# 1-Schematic_5_band_eq_adapter.net
KiCad netlist of a schematic drawn in EasyEDA
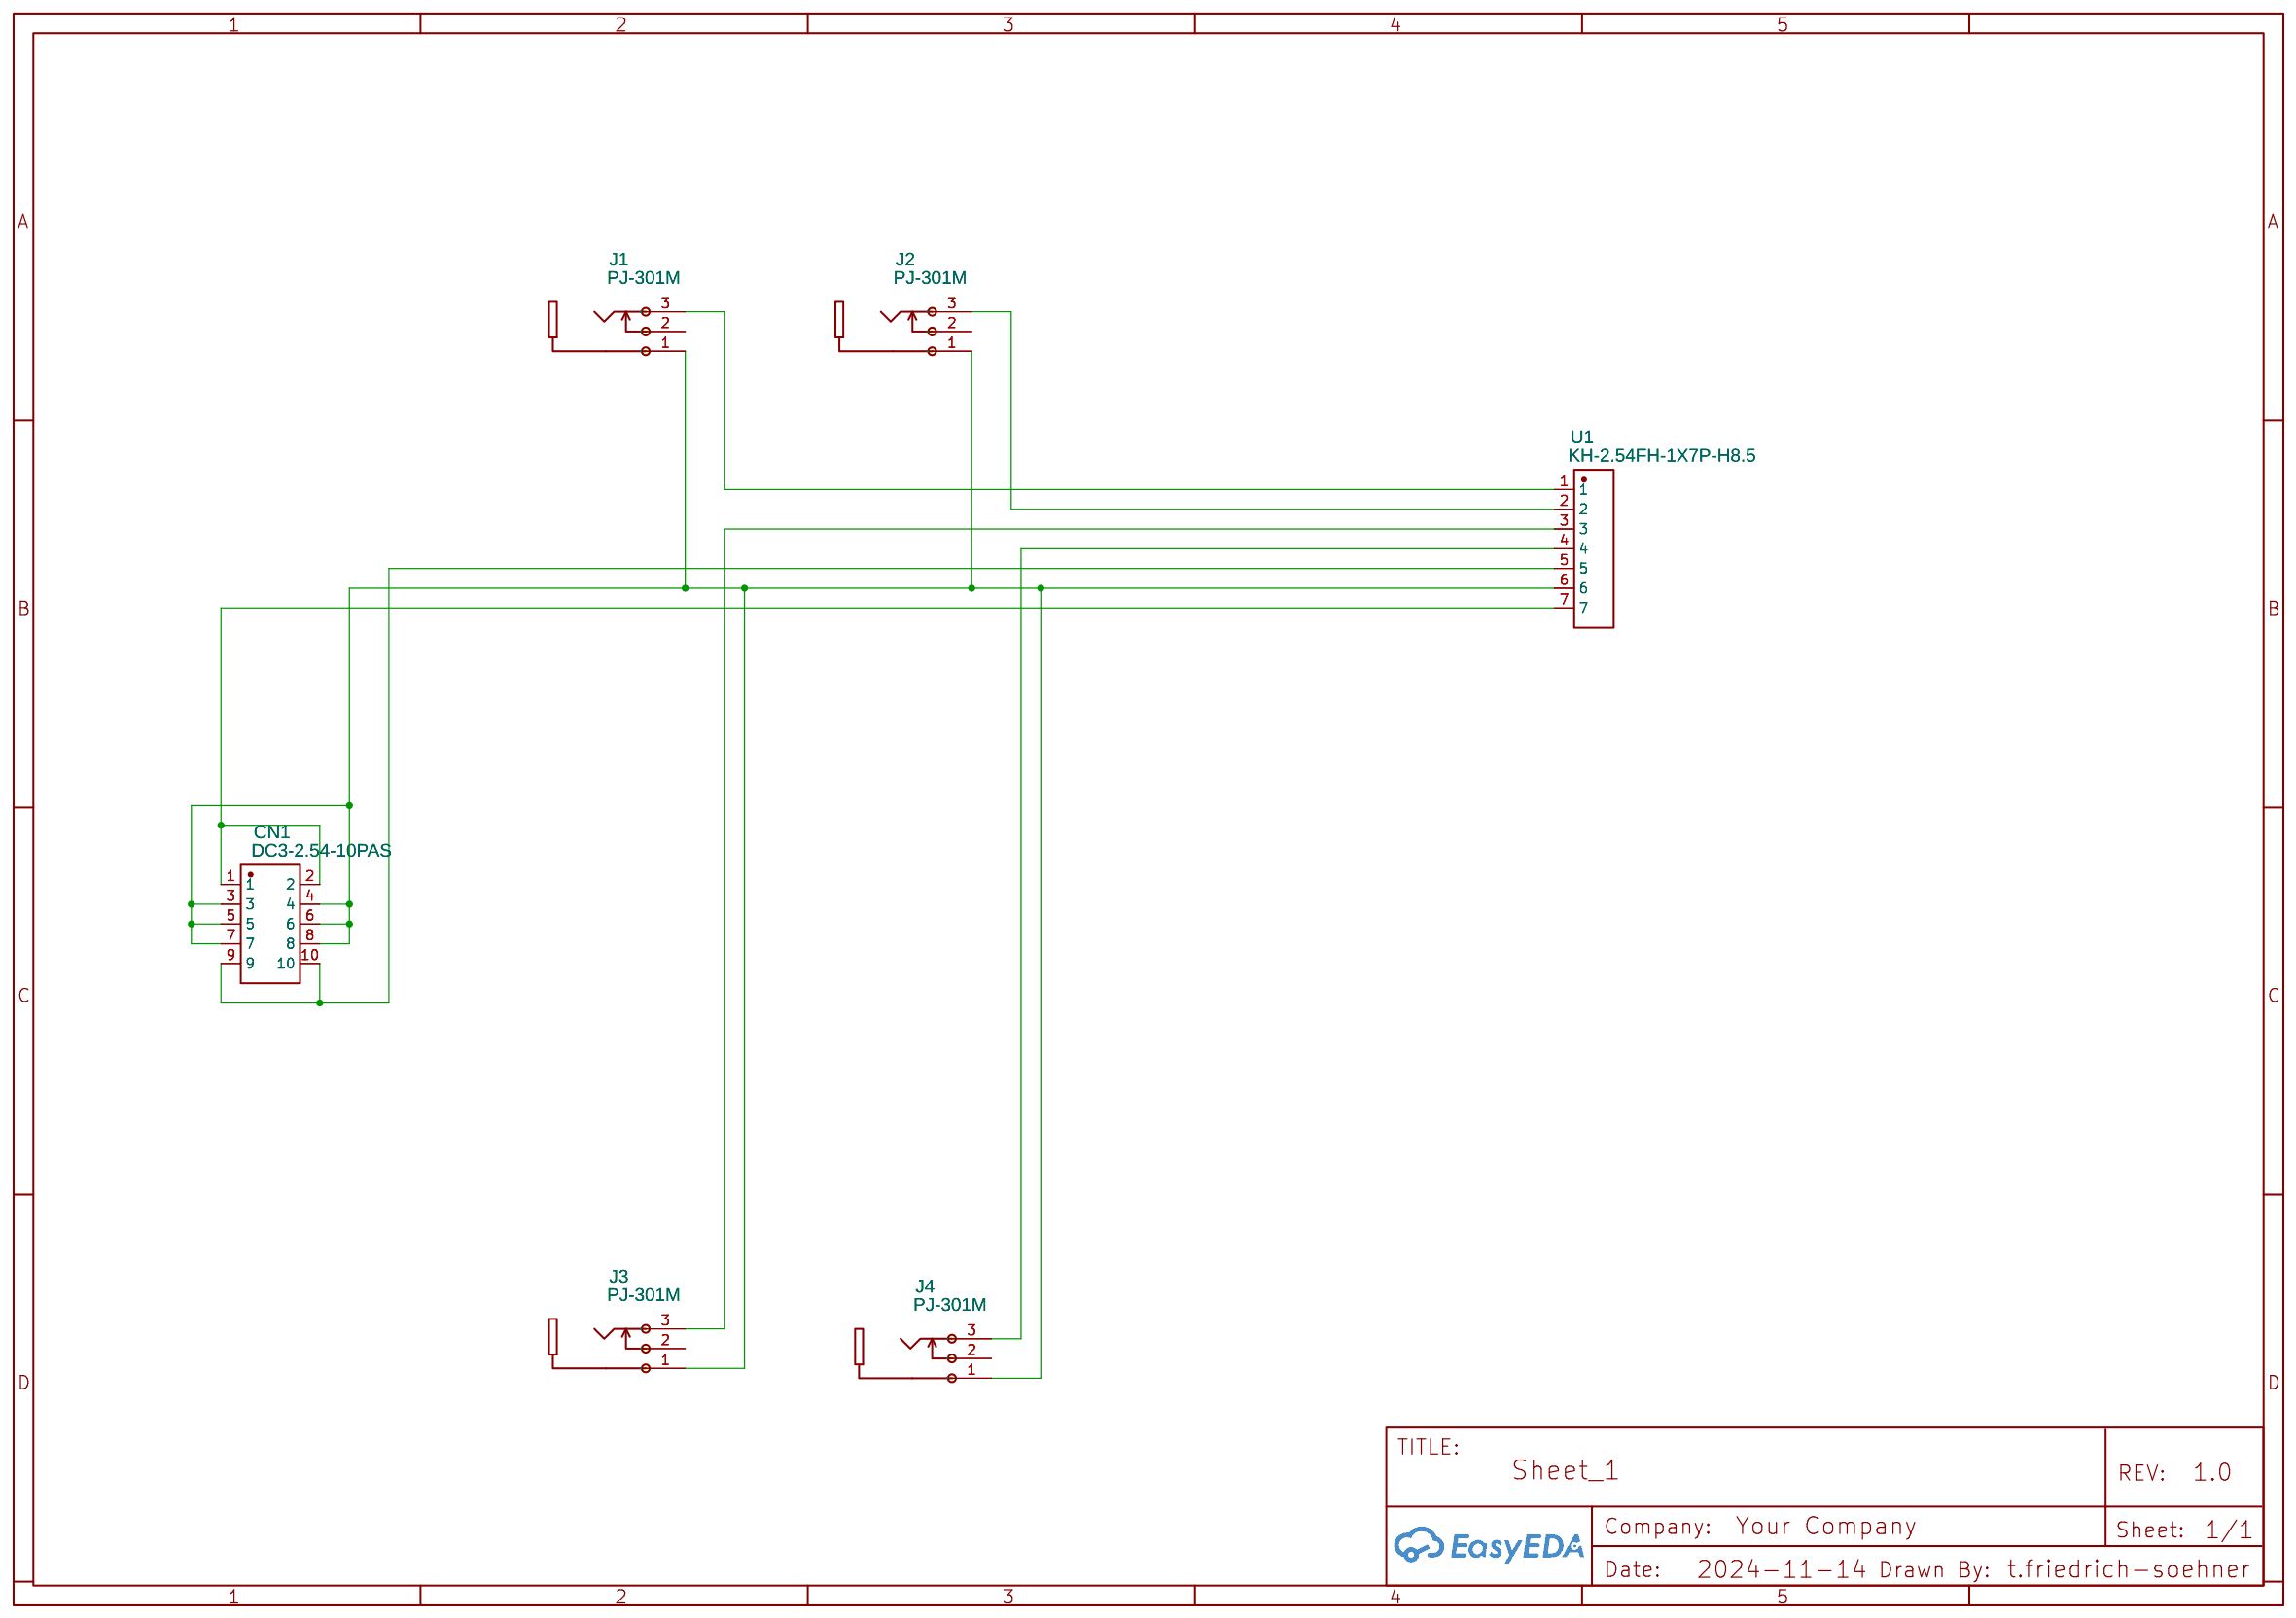
[diagram p0: schematic sheet]

(export (version "E")
  (design (tool "Eeschema 10.0.6"))
  (components
    (comp (ref "CN1")
      (value "DC3-2.54-10PAS")
      (fields (field (name "Manufacturer") "ZHOURI(洲日)"))
      (libsource (lib "") (part "DC3-2.54-10PAS"))
    )
    (comp (ref "J1") (value "PJ-301M") (libsource (lib "") (part "PJ-301M")))
    (comp (ref "J2") (value "PJ-301M") (libsource (lib "") (part "PJ-301M")))
    (comp (ref "J3") (value "PJ-301M") (libsource (lib "") (part "PJ-301M")))
    (comp (ref "J4") (value "PJ-301M") (libsource (lib "") (part "PJ-301M")))
    (comp (ref "U1")
      (value "KH-2.54FH-1X7P-H8.5")
      (fields (field (name "Manufacturer") "kinghelm(金航标)"))
      (libsource (lib "") (part "KH-2.54FH-1X7P-H8.5"))
    )
  )
  (nets
    (net (code "1") (name "Net-(CN1-Pad1)") (class "Default")
      (node (ref "CN1") (pin "1") (pinfunction "1_1") (pintype "unspecified"))
      (node (ref "CN1") (pin "2") (pinfunction "2_2") (pintype "unspecified"))
      (node (ref "U1") (pin "7") (pinfunction "7_7") (pintype "unspecified"))
    )
    (net (code "2") (name "Net-(CN1-Pad3)") (class "Default")
      (node (ref "CN1") (pin "3") (pinfunction "3_3") (pintype "unspecified"))
      (node (ref "CN1") (pin "4") (pinfunction "4_4") (pintype "unspecified"))
      (node (ref "CN1") (pin "5") (pinfunction "5_5") (pintype "unspecified"))
      (node (ref "CN1") (pin "6") (pinfunction "6_6") (pintype "unspecified"))
      (node (ref "CN1") (pin "7") (pinfunction "7_7") (pintype "unspecified"))
      (node (ref "CN1") (pin "8") (pinfunction "8_8") (pintype "unspecified"))
      (node (ref "J1") (pin "1") (pinfunction "1_1") (pintype "unspecified"))
      (node (ref "J2") (pin "1") (pinfunction "1_1") (pintype "unspecified"))
      (node (ref "J3") (pin "1") (pinfunction "1_1") (pintype "unspecified"))
      (node (ref "J4") (pin "1") (pinfunction "1_1") (pintype "unspecified"))
      (node (ref "U1") (pin "6") (pinfunction "6_6") (pintype "unspecified"))
    )
    (net (code "3") (name "Net-(CN1-Pad10)") (class "Default")
      (node (ref "CN1") (pin "10") (pinfunction "10_10") (pintype "unspecified"))
      (node (ref "CN1") (pin "9") (pinfunction "9_9") (pintype "unspecified"))
      (node (ref "U1") (pin "5") (pinfunction "5_5") (pintype "unspecified"))
    )
    (net (code "4") (name "Net-(J1-Pad3)") (class "Default")
      (node (ref "J1") (pin "3") (pinfunction "3_3") (pintype "unspecified"))
      (node (ref "U1") (pin "1") (pinfunction "1_1") (pintype "unspecified"))
    )
    (net (code "5") (name "Net-(J2-Pad3)") (class "Default")
      (node (ref "J2") (pin "3") (pinfunction "3_3") (pintype "unspecified"))
      (node (ref "U1") (pin "2") (pinfunction "2_2") (pintype "unspecified"))
    )
    (net (code "6") (name "Net-(J3-Pad3)") (class "Default")
      (node (ref "J3") (pin "3") (pinfunction "3_3") (pintype "unspecified"))
      (node (ref "U1") (pin "3") (pinfunction "3_3") (pintype "unspecified"))
    )
    (net (code "7") (name "Net-(J4-Pad3)") (class "Default")
      (node (ref "J4") (pin "3") (pinfunction "3_3") (pintype "unspecified"))
      (node (ref "U1") (pin "4") (pinfunction "4_4") (pintype "unspecified"))
    )
    (net (code "8") (name "unconnected-(J1-Pad2)") (class "Default")
      (node (ref "J1") (pin "2") (pinfunction "2_2") (pintype "unspecified"))
    )
    (net (code "9") (name "unconnected-(J2-Pad2)") (class "Default")
      (node (ref "J2") (pin "2") (pinfunction "2_2") (pintype "unspecified"))
    )
    (net (code "10") (name "unconnected-(J3-Pad2)") (class "Default")
      (node (ref "J3") (pin "2") (pinfunction "2_2") (pintype "unspecified"))
    )
    (net (code "11") (name "unconnected-(J4-Pad2)") (class "Default")
      (node (ref "J4") (pin "2") (pinfunction "2_2") (pintype "unspecified"))
    )
  )
)
